# CLK_GEN.net
KiCad netlist of a schematic drawn in Altium Designer
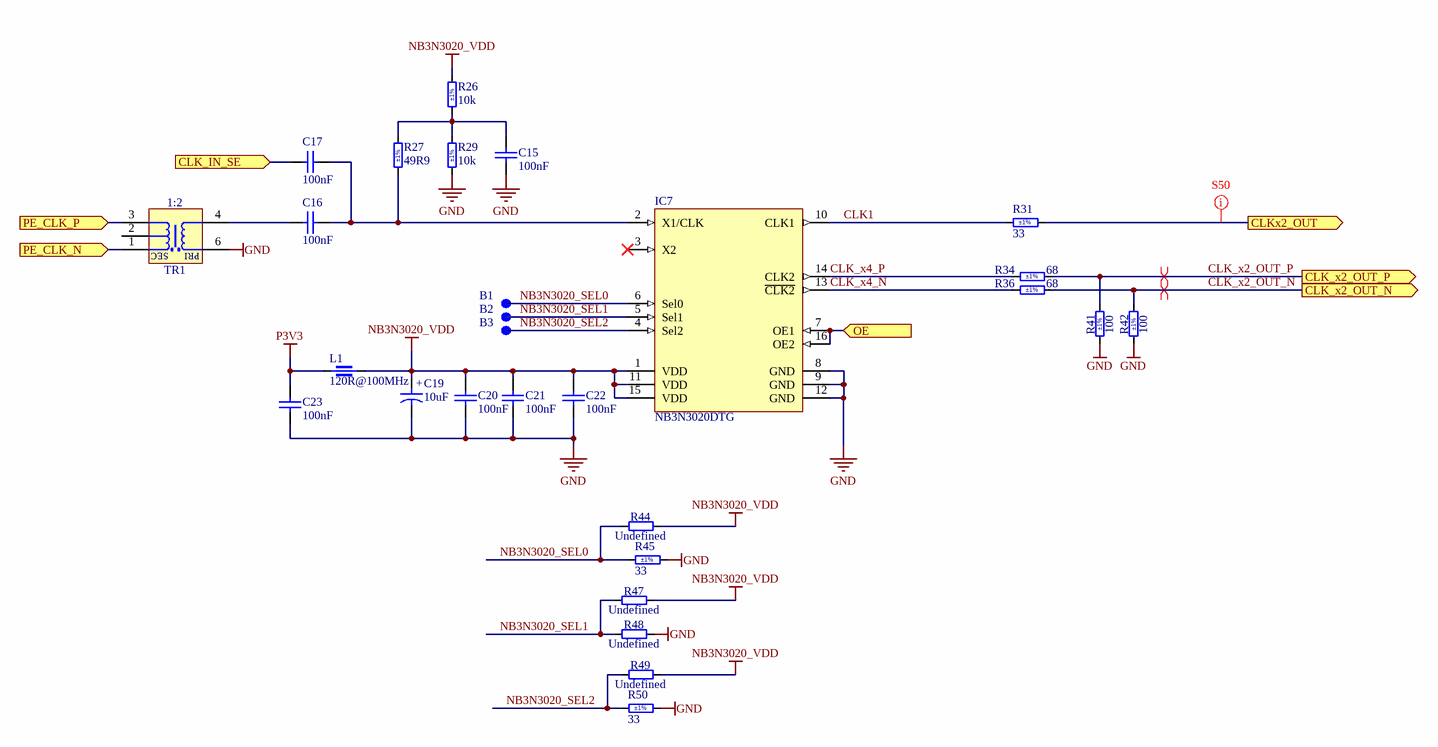
[diagram p0: CLK_GEN.SchDoc]

(export (version "E")
  (design (tool "Eeschema 10.0.6"))
  (components
    (comp (ref "B1")
      (value "SMD Pad")
      (footprint "C100")
      (description "Pad")
      (fields (field (name "PART NUMBER") "SMD_PAD_D1MM") (field (name "AUTHOR") "CERN DEM JLC"))
      (libsource (lib "Eletro-mechanical") (part "Single SMD Pad (Round)"))
    )
    (comp (ref "B2")
      (value "SMD Pad")
      (footprint "C100")
      (description "Pad")
      (fields (field (name "PART NUMBER") "SMD_PAD_D1MM") (field (name "AUTHOR") "CERN DEM JLC"))
      (libsource (lib "Eletro-mechanical") (part "Single SMD Pad (Round)"))
    )
    (comp (ref "B3")
      (value "SMD Pad")
      (footprint "C100")
      (description "Pad")
      (fields (field (name "PART NUMBER") "SMD_PAD_D1MM") (field (name "AUTHOR") "CERN DEM JLC"))
      (libsource (lib "Eletro-mechanical") (part "Single SMD Pad (Round)"))
    )
    (comp (ref "C15")
      (value "100nF")
      (footprint "CAPC1005X55N")
      (description "Non-polarised capacitor")
      (fields
        (field (name "PART NUMBER") "CC0402_100NF_50V_10%_X7R")
        (field (name "VOLTAGE") "50V")
        (field (name "AUTHOR") "CERN DEM MR")
      )
      (libsource (lib "Capacitors") (part "Capacitor - non polarized"))
    )
    (comp (ref "C16")
      (value "100nF")
      (footprint "CAPC1005X55N")
      (description "Non-polarised capacitor")
      (fields
        (field (name "PART NUMBER") "CC0402_100NF_50V_10%_X7R")
        (field (name "VOLTAGE") "50V")
        (field (name "AUTHOR") "CERN DEM MR")
      )
      (libsource (lib "Capacitors") (part "Capacitor - non polarized"))
    )
    (comp (ref "C17")
      (value "100nF")
      (footprint "CAPC1005X55N")
      (description "Non-polarised capacitor")
      (fields
        (field (name "PART NUMBER") "CC0402_100NF_50V_10%_X7R")
        (field (name "VOLTAGE") "50V")
        (field (name "AUTHOR") "CERN DEM MR")
      )
      (libsource (lib "Capacitors") (part "Capacitor - non polarized"))
    )
    (comp (ref "C19")
      (value "10uF")
      (footprint "CAPMP3216X180N")
      (description "Polarised capacitor")
      (fields
        (field (name "PART NUMBER") "CTE3216-18_10UF_16V_20%_AVX_TCJ")
        (field (name "VOLTAGE") "16V")
        (field (name "AUTHOR") "CERN DEM JLC")
      )
      (libsource (lib "Capacitors") (part "Capacitor - polarized"))
    )
    (comp (ref "C20")
      (value "100nF")
      (footprint "CAPC1005X55N")
      (description "Non-polarised capacitor")
      (fields
        (field (name "PART NUMBER") "CC0402_100NF_50V_10%_X7R")
        (field (name "VOLTAGE") "50V")
        (field (name "AUTHOR") "CERN DEM MR")
      )
      (libsource (lib "Capacitors") (part "Capacitor - non polarized"))
    )
    (comp (ref "C21")
      (value "100nF")
      (footprint "CAPC1005X55N")
      (description "Non-polarised capacitor")
      (fields
        (field (name "PART NUMBER") "CC0402_100NF_50V_10%_X7R")
        (field (name "VOLTAGE") "50V")
        (field (name "AUTHOR") "CERN DEM MR")
      )
      (libsource (lib "Capacitors") (part "Capacitor - non polarized"))
    )
    (comp (ref "C22")
      (value "100nF")
      (footprint "CAPC1005X55N")
      (description "Non-polarised capacitor")
      (fields
        (field (name "PART NUMBER") "CC0402_100NF_50V_10%_X7R")
        (field (name "VOLTAGE") "50V")
        (field (name "AUTHOR") "CERN DEM MR")
      )
      (libsource (lib "Capacitors") (part "Capacitor - non polarized"))
    )
    (comp (ref "C23")
      (value "100nF")
      (footprint "CAPC1005X55N")
      (description "Non-polarised capacitor")
      (fields
        (field (name "PART NUMBER") "CC0402_100NF_50V_10%_X7R")
        (field (name "VOLTAGE") "50V")
        (field (name "AUTHOR") "CERN DEM MR")
      )
      (libsource (lib "Capacitors") (part "Capacitor - non polarized"))
    )
    (comp (ref "IC7")
      (value "NB3N3020DTG")
      (footprint "TSOP65P640X120-16N")
      (description "Clock Generator 2MHz to 210MHz Input 210MHz Output 16-Pin TSSOP Tube")
      (fields (field (name "MANUFACTURER") "ON Semiconductor"))
      (libsource (lib "mb") (part "NB3N3020DTG"))
    )
    (comp (ref "L1")
      (value "120R@100MHz")
      (footprint "INDC1608X65N")
      (fields
        (field (name "PART NUMBER") "IND0603_MURATA_BLM18SG121TN1D")
        (field (name "POWER") "3A")
        (field (name "TOLERANCE") "±25%")
        (field (name "AUTHOR") "CERN DEM JLC")
      )
      (libsource (lib "Inductors & Transformers") (part "Ferrite Bead"))
    )
    (comp (ref "R26")
      (value "10k")
      (footprint "RESC1608X55N")
      (description "Resistor - 1%")
      (fields
        (field (name "TOLERANCE") "±1%")
        (field (name "PART NUMBER") "R0603_10K_1%_0.1W_100PPM")
        (field (name "POWER") "0.1W")
        (field (name "AUTHOR") "CERN DEM JLC")
      )
      (libsource (lib "Resistors") (part "Resistor - 1%"))
    )
    (comp (ref "R27")
      (value "49R9")
      (footprint "RESC1005X40N")
      (description "Resistor - 1%")
      (fields
        (field (name "TOLERANCE") "±1%")
        (field (name "PART NUMBER") "R0402_49R9_1%_0.0625W_100PPM")
        (field (name "POWER") "0.0625W")
        (field (name "AUTHOR") "CERN DEM JLC")
      )
      (libsource (lib "Resistors") (part "Resistor - 1%"))
    )
    (comp (ref "R29")
      (value "10k")
      (footprint "RESC1608X55N")
      (description "Resistor - 1%")
      (fields
        (field (name "TOLERANCE") "±1%")
        (field (name "PART NUMBER") "R0603_10K_1%_0.1W_100PPM")
        (field (name "POWER") "0.1W")
        (field (name "AUTHOR") "CERN DEM JLC")
      )
      (libsource (lib "Resistors") (part "Resistor - 1%"))
    )
    (comp (ref "R31")
      (value "33")
      (footprint "RESC1005X40N")
      (description "Resistor - 1%")
      (fields
        (field (name "TOLERANCE") "±1%")
        (field (name "PART NUMBER") "R0402_33R_1%_0.0625W_100PPM")
        (field (name "POWER") "0.0625W")
        (field (name "AUTHOR") "CERN DEM JLC")
      )
      (libsource (lib "Resistors") (part "Resistor - 1%"))
    )
    (comp (ref "R34")
      (value "68")
      (footprint "RESC1005X40N")
      (description "Resistor - 1%")
      (fields
        (field (name "TOLERANCE") "±1%")
        (field (name "PART NUMBER") "R0402_68R_1%_0.0625W_100PPM")
        (field (name "POWER") "0.0625W")
        (field (name "AUTHOR") "CERN DEM JLC")
      )
      (libsource (lib "Resistors") (part "Resistor - 1%"))
    )
    (comp (ref "R36")
      (value "68")
      (footprint "RESC1005X40N")
      (description "Resistor - 1%")
      (fields
        (field (name "TOLERANCE") "±1%")
        (field (name "PART NUMBER") "R0402_68R_1%_0.0625W_100PPM")
        (field (name "POWER") "0.0625W")
        (field (name "AUTHOR") "CERN DEM JLC")
      )
      (libsource (lib "Resistors") (part "Resistor - 1%"))
    )
    (comp (ref "R41")
      (value "100")
      (footprint "RESC1005X40N")
      (description "Resistor - 1%")
      (fields
        (field (name "TOLERANCE") "±1%")
        (field (name "PART NUMBER") "R0402_100R_1%_0.0625W_100PPM")
        (field (name "POWER") "0.0625W")
        (field (name "AUTHOR") "CERN DEM JLC")
      )
      (libsource (lib "Resistors") (part "Resistor - 1%"))
    )
    (comp (ref "R42")
      (value "100")
      (footprint "RESC1005X40N")
      (description "Resistor - 1%")
      (fields
        (field (name "TOLERANCE") "±1%")
        (field (name "PART NUMBER") "R0402_100R_1%_0.0625W_100PPM")
        (field (name "POWER") "0.0625W")
        (field (name "AUTHOR") "CERN DEM JLC")
      )
      (libsource (lib "Resistors") (part "Resistor - 1%"))
    )
    (comp (ref "R44")
      (value "Undefined")
      (footprint "RESC1608X55N")
      (description "Resistor")
      (fields (field (name "PART NUMBER") "R0603_NO-VALUE") (field (name "AUTHOR") "CERN DEM JLC"))
      (libsource (lib "Resistors") (part "Resistor"))
    )
    (comp (ref "R45")
      (value "33")
      (footprint "RESC1005X40N")
      (description "Resistor - 1%")
      (fields
        (field (name "TOLERANCE") "±1%")
        (field (name "PART NUMBER") "R0402_33R_1%_0.0625W_100PPM")
        (field (name "POWER") "0.0625W")
        (field (name "AUTHOR") "CERN DEM JLC")
      )
      (libsource (lib "Resistors") (part "Resistor - 1%"))
    )
    (comp (ref "R47")
      (value "Undefined")
      (footprint "RESC1608X55N")
      (description "Resistor")
      (fields (field (name "PART NUMBER") "R0603_NO-VALUE") (field (name "AUTHOR") "CERN DEM JLC"))
      (libsource (lib "Resistors") (part "Resistor"))
    )
    (comp (ref "R48")
      (value "Undefined")
      (footprint "RESC1608X55N")
      (description "Resistor")
      (fields (field (name "PART NUMBER") "R0603_NO-VALUE") (field (name "AUTHOR") "CERN DEM JLC"))
      (libsource (lib "Resistors") (part "Resistor"))
    )
    (comp (ref "R49")
      (value "Undefined")
      (footprint "RESC1608X55N")
      (description "Resistor")
      (fields (field (name "PART NUMBER") "R0603_NO-VALUE") (field (name "AUTHOR") "CERN DEM JLC"))
      (libsource (lib "Resistors") (part "Resistor"))
    )
    (comp (ref "R50")
      (value "33")
      (footprint "RESC1005X40N")
      (description "Resistor - 1%")
      (fields
        (field (name "TOLERANCE") "±1%")
        (field (name "PART NUMBER") "R0402_33R_1%_0.0625W_100PPM")
        (field (name "POWER") "0.0625W")
        (field (name "AUTHOR") "CERN DEM JLC")
      )
      (libsource (lib "Resistors") (part "Resistor - 1%"))
    )
    (comp (ref "TR1")
      (value "1:2")
      (footprint "XFMR_MINI-CIRCUITS_DB714")
      (description "50 Ohms 3 to 300MHz RF Transformer")
      (fields
        (field (name "PART NUMBER") "XFMR_MINI-CIRCUITS_TCM2-1T")
        (field (name "POWER") "0.25W")
        (field (name "AUTHOR") "CERN DEM HF")
      )
      (libsource (lib "Inductors & Transformers") (part "XFMR_MINI-CIRCUITS_TCM2-1T"))
    )
  )
  (nets
    (net (code "1") (name "/CLK1") (class "Default")
      (node (ref "IC7") (pin "10") (pinfunction "CLK1_10") (pintype "output"))
      (node (ref "R31") (pin "1") (pinfunction "1_1") (pintype "passive"))
    )
    (net (code "2") (name "/CLK_IN_SE") (class "Default")
      (node (ref "C17") (pin "1") (pinfunction "1_1") (pintype "passive"))
    )
    (net (code "3") (name "/CLK_x2_OUT_N") (class "Default")
      (node (ref "R36") (pin "2") (pinfunction "2_2") (pintype "passive"))
      (node (ref "R42") (pin "2") (pinfunction "2_2") (pintype "passive"))
    )
    (net (code "4") (name "/CLK_x2_OUT_P") (class "Default")
      (node (ref "R34") (pin "2") (pinfunction "2_2") (pintype "passive"))
      (node (ref "R41") (pin "2") (pinfunction "2_2") (pintype "passive"))
    )
    (net (code "5") (name "/CLK_x4_N") (class "Default")
      (node (ref "IC7") (pin "13") (pinfunction "~{CLK2}_13") (pintype "output"))
      (node (ref "R36") (pin "1") (pinfunction "1_1") (pintype "passive"))
    )
    (net (code "6") (name "/CLK_x4_P") (class "Default")
      (node (ref "IC7") (pin "14") (pinfunction "CLK2_14") (pintype "output"))
      (node (ref "R34") (pin "1") (pinfunction "1_1") (pintype "passive"))
    )
    (net (code "7") (name "/CLKx2_OUT") (class "Default")
      (node (ref "R31") (pin "2") (pinfunction "2_2") (pintype "passive"))
    )
    (net (code "8") (name "/NB3N3020_SEL0") (class "Default")
      (node (ref "B1") (pin "1") (pinfunction "1_1") (pintype "bidirectional"))
      (node (ref "IC7") (pin "6") (pinfunction "Sel0_6") (pintype "input"))
      (node (ref "R44") (pin "1") (pinfunction "1_1") (pintype "passive"))
      (node (ref "R45") (pin "1") (pinfunction "1_1") (pintype "passive"))
    )
    (net (code "9") (name "/NB3N3020_SEL1") (class "Default")
      (node (ref "B2") (pin "1") (pinfunction "1_1") (pintype "bidirectional"))
      (node (ref "IC7") (pin "5") (pinfunction "Sel1_5") (pintype "input"))
      (node (ref "R47") (pin "1") (pinfunction "1_1") (pintype "passive"))
      (node (ref "R48") (pin "1") (pinfunction "1_1") (pintype "passive"))
    )
    (net (code "10") (name "/NB3N3020_SEL2") (class "Default")
      (node (ref "B3") (pin "1") (pinfunction "1_1") (pintype "bidirectional"))
      (node (ref "IC7") (pin "4") (pinfunction "Sel2_4") (pintype "input"))
      (node (ref "R49") (pin "1") (pinfunction "1_1") (pintype "passive"))
      (node (ref "R50") (pin "1") (pinfunction "1_1") (pintype "passive"))
    )
    (net (code "11") (name "/OE") (class "Default")
      (node (ref "IC7") (pin "16") (pinfunction "OE2_16") (pintype "input"))
      (node (ref "IC7") (pin "7") (pinfunction "OE1_7") (pintype "input"))
    )
    (net (code "12") (name "/PE_CLK_N") (class "Default")
      (node (ref "TR1") (pin "1") (pinfunction "SDOT_1") (pintype "passive"))
    )
    (net (code "13") (name "/PE_CLK_P") (class "Default")
      (node (ref "TR1") (pin "3") (pinfunction "S_3") (pintype "passive"))
    )
    (net (code "14") (name "GND") (class "Default")
      (node (ref "C15") (pin "1") (pinfunction "1_1") (pintype "passive"))
      (node (ref "C19") (pin "2") (pinfunction "2_2") (pintype "passive"))
      (node (ref "C20") (pin "1") (pinfunction "1_1") (pintype "passive"))
      (node (ref "C21") (pin "1") (pinfunction "1_1") (pintype "passive"))
      (node (ref "C22") (pin "1") (pinfunction "1_1") (pintype "passive"))
      (node (ref "C23") (pin "1") (pinfunction "1_1") (pintype "passive"))
      (node (ref "IC7") (pin "12") (pinfunction "GND_12") (pintype "power_in"))
      (node (ref "IC7") (pin "8") (pinfunction "GND_8") (pintype "power_in"))
      (node (ref "IC7") (pin "9") (pinfunction "GND_9") (pintype "power_in"))
      (node (ref "R29") (pin "1") (pinfunction "1_1") (pintype "passive"))
      (node (ref "R41") (pin "1") (pinfunction "1_1") (pintype "passive"))
      (node (ref "R42") (pin "1") (pinfunction "1_1") (pintype "passive"))
      (node (ref "R45") (pin "2") (pinfunction "2_2") (pintype "passive"))
      (node (ref "R48") (pin "2") (pinfunction "2_2") (pintype "passive"))
      (node (ref "R50") (pin "2") (pinfunction "2_2") (pintype "passive"))
      (node (ref "TR1") (pin "6") (pinfunction "PDOT_6") (pintype "passive"))
    )
    (net (code "15") (name "NB3N3020_VDD") (class "Default")
      (node (ref "C19") (pin "1") (pinfunction "1_1") (pintype "passive"))
      (node (ref "C20") (pin "2") (pinfunction "2_2") (pintype "passive"))
      (node (ref "C21") (pin "2") (pinfunction "2_2") (pintype "passive"))
      (node (ref "C22") (pin "2") (pinfunction "2_2") (pintype "passive"))
      (node (ref "IC7") (pin "1") (pinfunction "VDD_1") (pintype "power_in"))
      (node (ref "IC7") (pin "11") (pinfunction "VDD_11") (pintype "power_in"))
      (node (ref "IC7") (pin "15") (pinfunction "VDD_15") (pintype "power_in"))
      (node (ref "L1") (pin "2") (pinfunction "2_2") (pintype "passive"))
      (node (ref "R26") (pin "2") (pinfunction "2_2") (pintype "passive"))
      (node (ref "R44") (pin "2") (pinfunction "2_2") (pintype "passive"))
      (node (ref "R47") (pin "2") (pinfunction "2_2") (pintype "passive"))
      (node (ref "R49") (pin "2") (pinfunction "2_2") (pintype "passive"))
    )
    (net (code "16") (name "Net-(C15-Pad2)") (class "Default")
      (node (ref "C15") (pin "2") (pinfunction "2_2") (pintype "passive"))
      (node (ref "R26") (pin "1") (pinfunction "1_1") (pintype "passive"))
      (node (ref "R27") (pin "2") (pinfunction "2_2") (pintype "passive"))
      (node (ref "R29") (pin "2") (pinfunction "2_2") (pintype "passive"))
    )
    (net (code "17") (name "Net-(IC7-X1{slash}CLK)") (class "Default")
      (node (ref "C16") (pin "2") (pinfunction "2_2") (pintype "passive"))
      (node (ref "C17") (pin "2") (pinfunction "2_2") (pintype "passive"))
      (node (ref "IC7") (pin "2") (pinfunction "X1/CLK_2") (pintype "input"))
      (node (ref "R27") (pin "1") (pinfunction "1_1") (pintype "passive"))
    )
    (net (code "18") (name "Net-(TR1-P)") (class "Default")
      (node (ref "C16") (pin "1") (pinfunction "1_1") (pintype "passive"))
      (node (ref "TR1") (pin "4") (pinfunction "P_4") (pintype "passive"))
    )
    (net (code "19") (name "P3V3") (class "Default")
      (node (ref "C23") (pin "2") (pinfunction "2_2") (pintype "passive"))
      (node (ref "L1") (pin "1") (pinfunction "1_1") (pintype "passive"))
    )
    (net (code "20") (name "unconnected-(IC7-X2-Pad3)") (class "Default")
      (node (ref "IC7") (pin "3") (pinfunction "X2_3") (pintype "input+no_connect"))
    )
    (net (code "21") (name "unconnected-(TR1-NU-Pad2)") (class "Default")
      (node (ref "TR1") (pin "2") (pinfunction "NU_2") (pintype "passive"))
    )
  )
)
